# BT-PROGRAMER.net
KiCad netlist of a schematic drawn in EAGLE
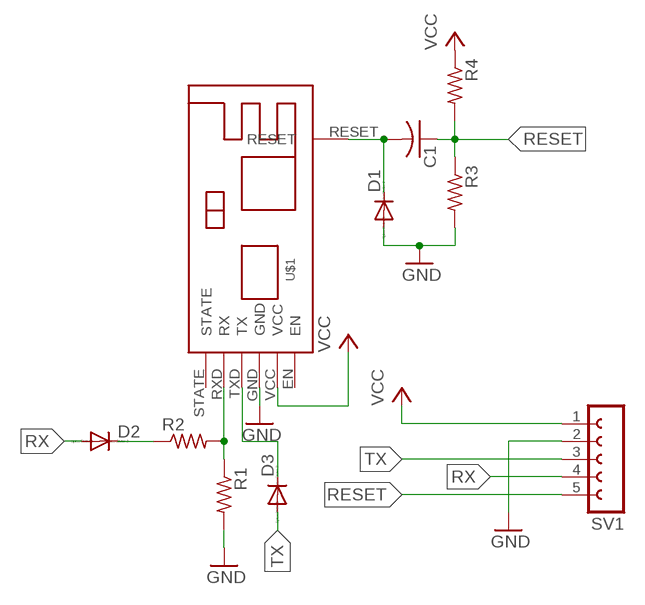
[diagram p0: schematic, sheet 1]

(export (version "E")
  (design (tool "Eeschema 10.0.6"))
  (components
    (comp (ref "C1")
      (value "C-USC0603")
      (footprint "eagle-import:C0603")
      (libsource (lib "eagle-import") (part "C-USC0603"))
    )
    (comp (ref "D1")
      (value "DIODE-DO-214AC")
      (footprint "eagle-import:DO-214AC")
      (libsource (lib "eagle-import") (part "DIODE-DO-214AC"))
    )
    (comp (ref "D2")
      (value "DIODE-DO-214AC")
      (footprint "eagle-import:DO-214AC")
      (libsource (lib "eagle-import") (part "DIODE-DO-214AC"))
    )
    (comp (ref "D3")
      (value "DIODE-DO-214AC")
      (footprint "eagle-import:DO-214AC")
      (libsource (lib "eagle-import") (part "DIODE-DO-214AC"))
    )
    (comp (ref "R1")
      (value "R-US_M1206")
      (footprint "eagle-import:M1206")
      (libsource (lib "eagle-import") (part "R-US_M1206"))
    )
    (comp (ref "R2")
      (value "R-US_M1206")
      (footprint "eagle-import:M1206")
      (libsource (lib "eagle-import") (part "R-US_M1206"))
    )
    (comp (ref "R3")
      (value "R-US_M1206")
      (footprint "eagle-import:M1206")
      (libsource (lib "eagle-import") (part "R-US_M1206"))
    )
    (comp (ref "R4")
      (value "R-US_M1206")
      (footprint "eagle-import:M1206")
      (libsource (lib "eagle-import") (part "R-US_M1206"))
    )
    (comp (ref "SV1")
      (value "FE05-1")
      (footprint "eagle-import:FE05-1")
      (libsource (lib "eagle-import") (part "FE05-1"))
    )
    (comp (ref "U$1")
      (value "HC-05-PROG")
      (footprint "eagle-import:HC-05-PROG")
      (libsource (lib "eagle-import") (part "HC-05-PROG"))
    )
  )
  (nets
    (net (code "1") (name "GND") (class "Default")
      (node (ref "D1") (pin "A") (pinfunction "A_A") (pintype "passive"))
      (node (ref "R1") (pin "2") (pinfunction "2_2") (pintype "passive"))
      (node (ref "R3") (pin "2") (pinfunction "2_2") (pintype "passive"))
      (node (ref "SV1") (pin "2") (pinfunction "2_2") (pintype "passive"))
      (node (ref "U$1") (pin "GND") (pinfunction "GND_GND") (pintype "bidirectional"))
    )
    (net (code "2") (name "Net-(C1-Pad2)") (class "Default")
      (node (ref "C1") (pin "2") (pinfunction "2_2") (pintype "passive"))
      (node (ref "D1") (pin "C") (pinfunction "C_C") (pintype "passive"))
      (node (ref "U$1") (pin "RESET") (pinfunction "RESET_RESET") (pintype "bidirectional"))
    )
    (net (code "3") (name "Net-(D2-PadC)") (class "Default")
      (node (ref "D2") (pin "C") (pinfunction "C_C") (pintype "passive"))
      (node (ref "R2") (pin "1") (pinfunction "1_1") (pintype "passive"))
    )
    (net (code "4") (name "Net-(U$1-RX)") (class "Default")
      (node (ref "R1") (pin "1") (pinfunction "1_1") (pintype "passive"))
      (node (ref "R2") (pin "2") (pinfunction "2_2") (pintype "passive"))
      (node (ref "U$1") (pin "RXD") (pinfunction "RX_RXD") (pintype "bidirectional"))
    )
    (net (code "5") (name "Net-(U$1-TX)") (class "Default")
      (node (ref "D3") (pin "C") (pinfunction "C_C") (pintype "passive"))
      (node (ref "U$1") (pin "TXD") (pinfunction "TX_TXD") (pintype "bidirectional"))
    )
    (net (code "6") (name "RESET") (class "Default")
      (node (ref "C1") (pin "1") (pinfunction "1_1") (pintype "passive"))
      (node (ref "R3") (pin "1") (pinfunction "1_1") (pintype "passive"))
      (node (ref "R4") (pin "2") (pinfunction "2_2") (pintype "passive"))
      (node (ref "SV1") (pin "5") (pinfunction "5_5") (pintype "passive"))
    )
    (net (code "7") (name "RX") (class "Default")
      (node (ref "D2") (pin "A") (pinfunction "A_A") (pintype "passive"))
      (node (ref "SV1") (pin "4") (pinfunction "4_4") (pintype "passive"))
    )
    (net (code "8") (name "TX") (class "Default")
      (node (ref "D3") (pin "A") (pinfunction "A_A") (pintype "passive"))
      (node (ref "SV1") (pin "3") (pinfunction "3_3") (pintype "passive"))
    )
    (net (code "9") (name "VCC") (class "Default")
      (node (ref "R4") (pin "1") (pinfunction "1_1") (pintype "passive"))
      (node (ref "SV1") (pin "1") (pinfunction "1_1") (pintype "passive"))
      (node (ref "U$1") (pin "VCC") (pinfunction "VCC_VCC") (pintype "bidirectional"))
    )
    (net (code "10") (name "unconnected-(U$1-PadEN)") (class "Default")
      (node (ref "U$1") (pin "EN") (pinfunction "EN_EN") (pintype "bidirectional"))
    )
    (net (code "11") (name "unconnected-(U$1-PadSTATE)") (class "Default")
      (node (ref "U$1") (pin "STATE") (pinfunction "STATE_STATE") (pintype "bidirectional"))
    )
  )
)
